# Arturo_Veras.net
KiCad netlist of a schematic drawn in EAGLE
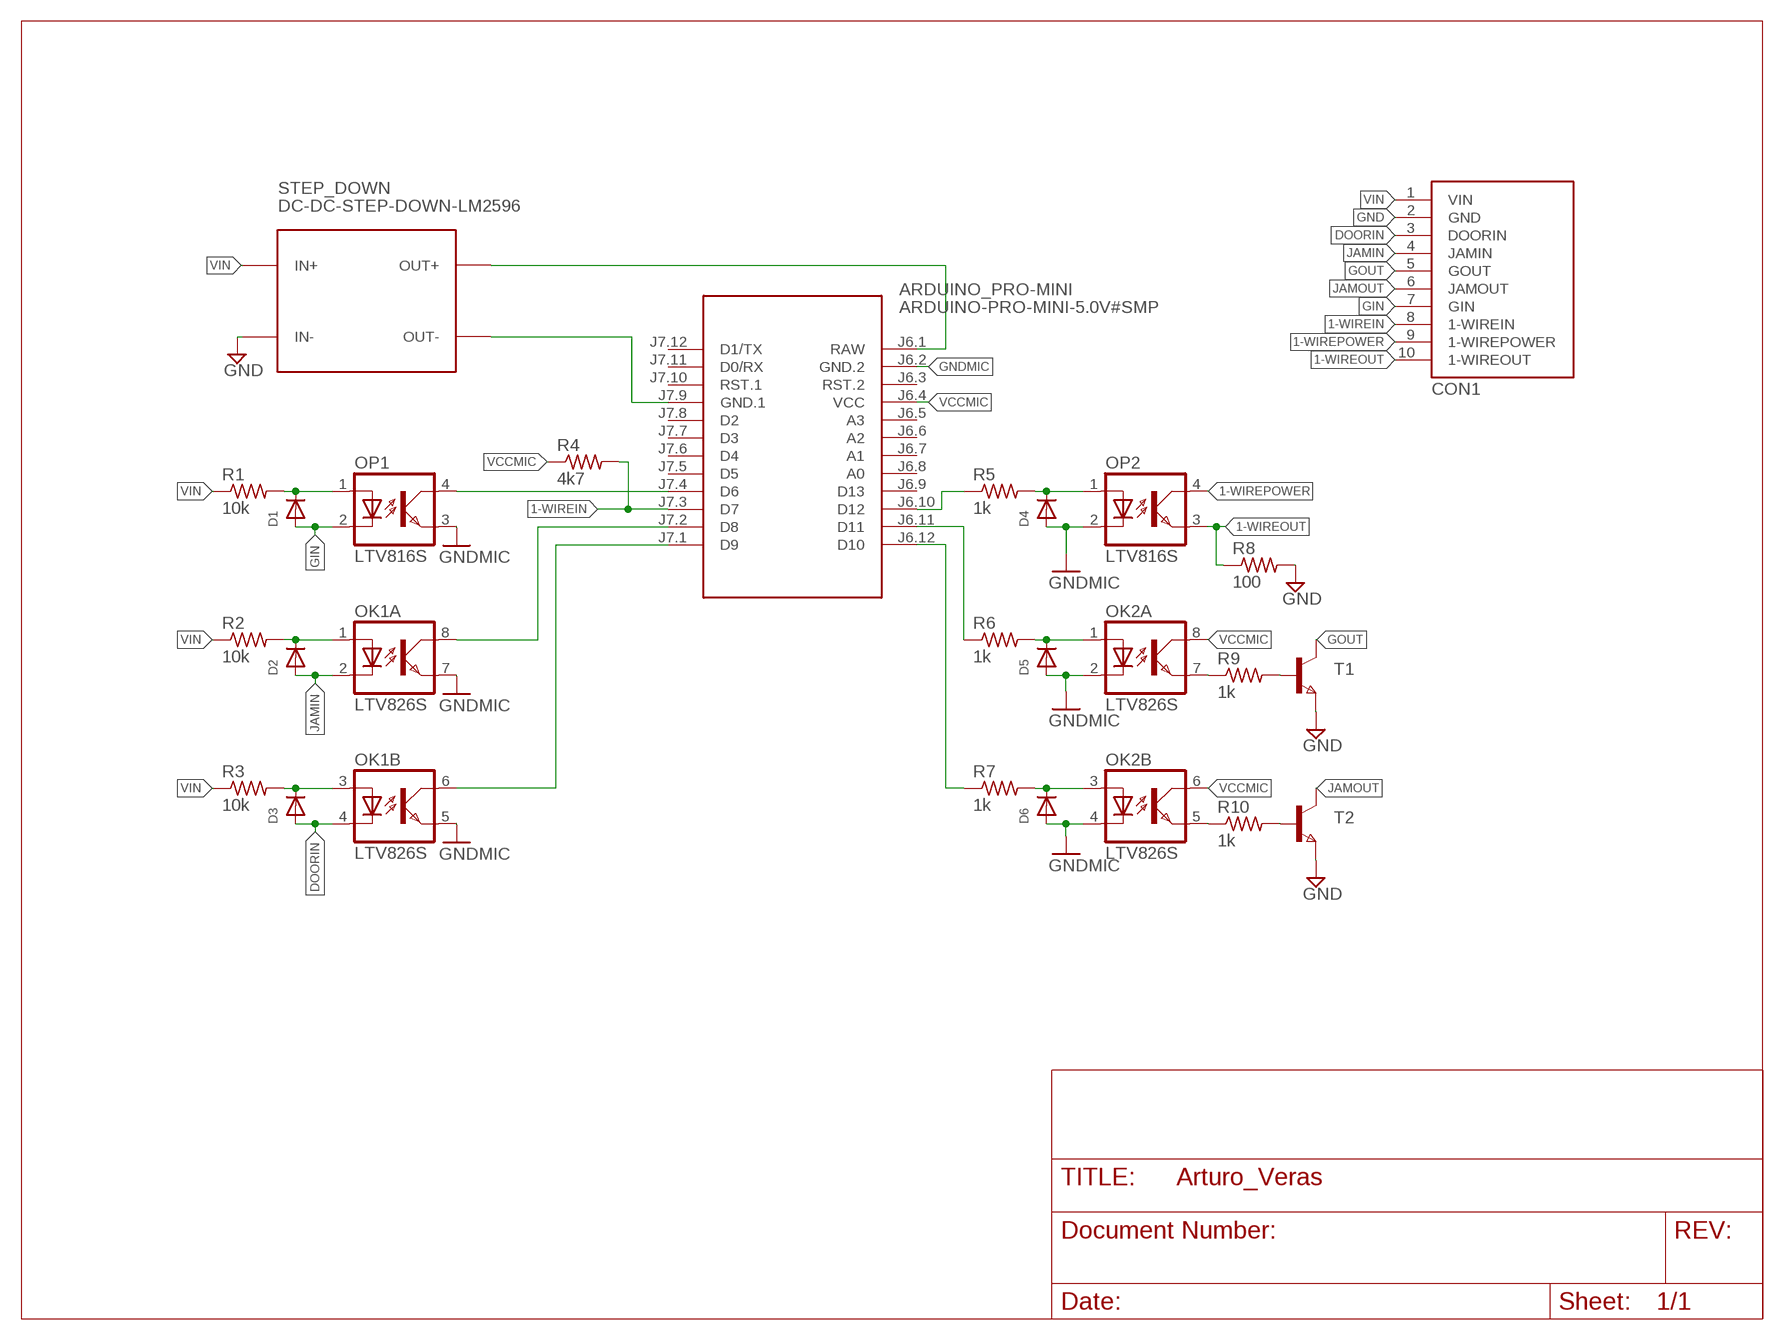
[diagram p0: schematic, sheet 1]

(export (version "E")
  (design (tool "Eeschema 10.0.6"))
  (components
    (comp (ref "ARDUINO_PRO-MINI")
      (value "ARDUINO-PRO-MINI-5.0V#SMP")
      (footprint "eagle-import:ARDUINO-PRO-MINI#SMP")
      (libsource (lib "eagle-import") (part "ARDUINO-PRO-MINI-#SMP5.0V"))
    )
    (comp (ref "CON1")
      (value "TIN_HEADER_10POS")
      (footprint "eagle-import:MICRO_MATE_N_LOK_TRUEHOLE_10POS")
      (libsource (lib "eagle-import") (part "TIN_HEADER_10POS"))
    )
    (comp (ref "D1")
      (value "DIODESOD-323F")
      (footprint "eagle-import:SOD-323F")
      (libsource (lib "eagle-import") (part "DIODESOD-323F"))
    )
    (comp (ref "D2")
      (value "DIODESOD-323F")
      (footprint "eagle-import:SOD-323F")
      (libsource (lib "eagle-import") (part "DIODESOD-323F"))
    )
    (comp (ref "D3")
      (value "DIODESOD-323F")
      (footprint "eagle-import:SOD-323F")
      (libsource (lib "eagle-import") (part "DIODESOD-323F"))
    )
    (comp (ref "D4")
      (value "DIODESOD-323F")
      (footprint "eagle-import:SOD-323F")
      (libsource (lib "eagle-import") (part "DIODESOD-323F"))
    )
    (comp (ref "D5")
      (value "DIODESOD-323F")
      (footprint "eagle-import:SOD-323F")
      (libsource (lib "eagle-import") (part "DIODESOD-323F"))
    )
    (comp (ref "D6")
      (value "DIODESOD-323F")
      (footprint "eagle-import:SOD-323F")
      (libsource (lib "eagle-import") (part "DIODESOD-323F"))
    )
    (comp (ref "OK1")
      (value "LTV826S")
      (footprint "eagle-import:DIL8-SMD")
      (libsource (lib "eagle-import") (part "LTV826S"))
    )
    (comp (ref "OK2")
      (value "LTV826S")
      (footprint "eagle-import:DIL8-SMD")
      (libsource (lib "eagle-import") (part "LTV826S"))
    )
    (comp (ref "OP1")
      (value "LTV816S")
      (footprint "eagle-import:SMD4")
      (libsource (lib "eagle-import") (part "LTV816S"))
    )
    (comp (ref "OP2")
      (value "LTV816S")
      (footprint "eagle-import:SMD4")
      (libsource (lib "eagle-import") (part "LTV816S"))
    )
    (comp (ref "R1")
      (value "10k")
      (footprint "eagle-import:R0603")
      (libsource (lib "eagle-import") (part "R-US_R0603"))
    )
    (comp (ref "R2")
      (value "10k")
      (footprint "eagle-import:R0603")
      (libsource (lib "eagle-import") (part "R-US_R0603"))
    )
    (comp (ref "R3")
      (value "10k")
      (footprint "eagle-import:R0603")
      (libsource (lib "eagle-import") (part "R-US_R0603"))
    )
    (comp (ref "R4")
      (value "4k7")
      (footprint "eagle-import:R0603")
      (libsource (lib "eagle-import") (part "R-US_R0603"))
    )
    (comp (ref "R5")
      (value "1k")
      (footprint "eagle-import:R0603")
      (libsource (lib "eagle-import") (part "R-US_R0603"))
    )
    (comp (ref "R6")
      (value "1k")
      (footprint "eagle-import:R0603")
      (libsource (lib "eagle-import") (part "R-US_R0603"))
    )
    (comp (ref "R7")
      (value "1k")
      (footprint "eagle-import:R0603")
      (libsource (lib "eagle-import") (part "R-US_R0603"))
    )
    (comp (ref "R8")
      (value "100")
      (footprint "eagle-import:R0603")
      (libsource (lib "eagle-import") (part "R-US_R0603"))
    )
    (comp (ref "R9")
      (value "1k")
      (footprint "eagle-import:R0603")
      (libsource (lib "eagle-import") (part "R-US_R0603"))
    )
    (comp (ref "R10")
      (value "1k")
      (footprint "eagle-import:R0603")
      (libsource (lib "eagle-import") (part "R-US_R0603"))
    )
    (comp (ref "STEP_DOWN")
      (value "DC-DC-STEP-DOWN-LM2596")
      (footprint "eagle-import:DC-DC-STEP-DOWN-LM2596")
      (libsource (lib "eagle-import") (part "DC-DC-STEP-DOWN-LM2596"))
    )
    (comp (ref "T1")
      (value "PBSS4360Z")
      (footprint "eagle-import:SOT223")
      (libsource (lib "eagle-import") (part "PBSS4360Z"))
    )
    (comp (ref "T2")
      (value "PBSS4360Z")
      (footprint "eagle-import:SOT223")
      (libsource (lib "eagle-import") (part "PBSS4360Z"))
    )
  )
  (nets
    (net (code "1") (name "1-WIREIN") (class "Default")
      (node (ref "ARDUINO_PRO-MINI") (pin "J7.3") (pinfunction "D7_J7.3") (pintype "bidirectional"))
      (node (ref "CON1") (pin "8") (pinfunction "1-WIREIN_8") (pintype "bidirectional"))
      (node (ref "R4") (pin "2") (pinfunction "2_2") (pintype "passive"))
    )
    (net (code "2") (name "1-WIREOUT") (class "Default")
      (node (ref "CON1") (pin "10") (pinfunction "1-WIREOUT_10") (pintype "bidirectional"))
      (node (ref "OP2") (pin "3") (pinfunction "EMIT_3") (pintype "passive"))
      (node (ref "R8") (pin "1") (pinfunction "1_1") (pintype "passive"))
    )
    (net (code "3") (name "1-WIREPOWER") (class "Default")
      (node (ref "CON1") (pin "9") (pinfunction "1-WIREPOWER_9") (pintype "bidirectional"))
      (node (ref "OP2") (pin "4") (pinfunction "COL_4") (pintype "passive"))
    )
    (net (code "4") (name "DOORIN") (class "Default")
      (node (ref "CON1") (pin "3") (pinfunction "DOORIN_3") (pintype "bidirectional"))
      (node (ref "D3") (pin "A") (pinfunction "A_A") (pintype "passive"))
      (node (ref "OK1") (pin "4") (pinfunction "C_4") (pintype "passive"))
    )
    (net (code "5") (name "GIN") (class "Default")
      (node (ref "CON1") (pin "7") (pinfunction "GIN_7") (pintype "bidirectional"))
      (node (ref "D1") (pin "A") (pinfunction "A_A") (pintype "passive"))
      (node (ref "OP1") (pin "2") (pinfunction "C_2") (pintype "passive"))
    )
    (net (code "6") (name "GND") (class "Default")
      (node (ref "CON1") (pin "2") (pinfunction "GND_2") (pintype "bidirectional"))
      (node (ref "R8") (pin "2") (pinfunction "2_2") (pintype "passive"))
      (node (ref "STEP_DOWN") (pin "IN-") (pinfunction "IN-_IN-") (pintype "bidirectional"))
      (node (ref "T1") (pin "3") (pinfunction "E_3") (pintype "passive"))
      (node (ref "T2") (pin "3") (pinfunction "E_3") (pintype "passive"))
    )
    (net (code "7") (name "GNDMIC") (class "Default")
      (node (ref "ARDUINO_PRO-MINI") (pin "J6.2") (pinfunction "GND.2_J6.2") (pintype "power_in"))
      (node (ref "D4") (pin "A") (pinfunction "A_A") (pintype "passive"))
      (node (ref "D5") (pin "A") (pinfunction "A_A") (pintype "passive"))
      (node (ref "D6") (pin "A") (pinfunction "A_A") (pintype "passive"))
      (node (ref "OK1") (pin "5") (pinfunction "EMIT_5") (pintype "passive"))
      (node (ref "OK1") (pin "7") (pinfunction "EMIT_7") (pintype "passive"))
      (node (ref "OK2") (pin "2") (pinfunction "C_2") (pintype "passive"))
      (node (ref "OK2") (pin "4") (pinfunction "C_4") (pintype "passive"))
      (node (ref "OP1") (pin "3") (pinfunction "EMIT_3") (pintype "passive"))
      (node (ref "OP2") (pin "2") (pinfunction "C_2") (pintype "passive"))
    )
    (net (code "8") (name "GOUT") (class "Default")
      (node (ref "CON1") (pin "5") (pinfunction "GOUT_5") (pintype "bidirectional"))
      (node (ref "T1") (pin "2") (pinfunction "C_2") (pintype "passive"))
      (node (ref "T1") (pin "4") (pinfunction "C_4") (pintype "passive"))
    )
    (net (code "9") (name "JAMIN") (class "Default")
      (node (ref "CON1") (pin "4") (pinfunction "JAMIN_4") (pintype "bidirectional"))
      (node (ref "D2") (pin "A") (pinfunction "A_A") (pintype "passive"))
      (node (ref "OK1") (pin "2") (pinfunction "C_2") (pintype "passive"))
    )
    (net (code "10") (name "JAMOUT") (class "Default")
      (node (ref "CON1") (pin "6") (pinfunction "JAMOUT_6") (pintype "bidirectional"))
      (node (ref "T2") (pin "2") (pinfunction "C_2") (pintype "passive"))
      (node (ref "T2") (pin "4") (pinfunction "C_4") (pintype "passive"))
    )
    (net (code "11") (name "Net-(ARDUINO_PRO-MINI-D6)") (class "Default")
      (node (ref "ARDUINO_PRO-MINI") (pin "J7.4") (pinfunction "D6_J7.4") (pintype "bidirectional"))
      (node (ref "OP1") (pin "4") (pinfunction "COL_4") (pintype "passive"))
    )
    (net (code "12") (name "Net-(ARDUINO_PRO-MINI-D8)") (class "Default")
      (node (ref "ARDUINO_PRO-MINI") (pin "J7.2") (pinfunction "D8_J7.2") (pintype "bidirectional"))
      (node (ref "OK1") (pin "8") (pinfunction "COL_8") (pintype "passive"))
    )
    (net (code "13") (name "Net-(ARDUINO_PRO-MINI-D9)") (class "Default")
      (node (ref "ARDUINO_PRO-MINI") (pin "J7.1") (pinfunction "D9_J7.1") (pintype "bidirectional"))
      (node (ref "OK1") (pin "6") (pinfunction "COL_6") (pintype "passive"))
    )
    (net (code "14") (name "Net-(ARDUINO_PRO-MINI-D10)") (class "Default")
      (node (ref "ARDUINO_PRO-MINI") (pin "J6.12") (pinfunction "D10_J6.12") (pintype "bidirectional"))
      (node (ref "R7") (pin "1") (pinfunction "1_1") (pintype "passive"))
    )
    (net (code "15") (name "Net-(ARDUINO_PRO-MINI-D11)") (class "Default")
      (node (ref "ARDUINO_PRO-MINI") (pin "J6.11") (pinfunction "D11_J6.11") (pintype "bidirectional"))
      (node (ref "R6") (pin "1") (pinfunction "1_1") (pintype "passive"))
    )
    (net (code "16") (name "Net-(ARDUINO_PRO-MINI-D12)") (class "Default")
      (node (ref "ARDUINO_PRO-MINI") (pin "J6.10") (pinfunction "D12_J6.10") (pintype "bidirectional"))
      (node (ref "R5") (pin "1") (pinfunction "1_1") (pintype "passive"))
    )
    (net (code "17") (name "Net-(ARDUINO_PRO-MINI-GND.1)") (class "Default")
      (node (ref "ARDUINO_PRO-MINI") (pin "J7.9") (pinfunction "GND.1_J7.9") (pintype "power_in"))
      (node (ref "STEP_DOWN") (pin "OUT-") (pinfunction "OUT-_OUT-") (pintype "bidirectional"))
    )
    (net (code "18") (name "Net-(ARDUINO_PRO-MINI-RAW)") (class "Default")
      (node (ref "ARDUINO_PRO-MINI") (pin "J6.1") (pinfunction "RAW_J6.1") (pintype "power_in"))
      (node (ref "STEP_DOWN") (pin "OUT+") (pinfunction "OUT+_OUT+") (pintype "bidirectional"))
    )
    (net (code "19") (name "Net-(OK1A-A)") (class "Default")
      (node (ref "D2") (pin "C") (pinfunction "C_C") (pintype "passive"))
      (node (ref "OK1") (pin "1") (pinfunction "A_1") (pintype "passive"))
      (node (ref "R2") (pin "2") (pinfunction "2_2") (pintype "passive"))
    )
    (net (code "20") (name "Net-(OK1B-A)") (class "Default")
      (node (ref "D3") (pin "C") (pinfunction "C_C") (pintype "passive"))
      (node (ref "OK1") (pin "3") (pinfunction "A_3") (pintype "passive"))
      (node (ref "R3") (pin "2") (pinfunction "2_2") (pintype "passive"))
    )
    (net (code "21") (name "Net-(OK2A-A)") (class "Default")
      (node (ref "D5") (pin "C") (pinfunction "C_C") (pintype "passive"))
      (node (ref "OK2") (pin "1") (pinfunction "A_1") (pintype "passive"))
      (node (ref "R6") (pin "2") (pinfunction "2_2") (pintype "passive"))
    )
    (net (code "22") (name "Net-(OK2A-EMIT)") (class "Default")
      (node (ref "OK2") (pin "7") (pinfunction "EMIT_7") (pintype "passive"))
      (node (ref "R9") (pin "1") (pinfunction "1_1") (pintype "passive"))
    )
    (net (code "23") (name "Net-(OK2B-A)") (class "Default")
      (node (ref "D6") (pin "C") (pinfunction "C_C") (pintype "passive"))
      (node (ref "OK2") (pin "3") (pinfunction "A_3") (pintype "passive"))
      (node (ref "R7") (pin "2") (pinfunction "2_2") (pintype "passive"))
    )
    (net (code "24") (name "Net-(OK2B-EMIT)") (class "Default")
      (node (ref "OK2") (pin "5") (pinfunction "EMIT_5") (pintype "passive"))
      (node (ref "R10") (pin "1") (pinfunction "1_1") (pintype "passive"))
    )
    (net (code "25") (name "Net-(OP1-A)") (class "Default")
      (node (ref "D1") (pin "C") (pinfunction "C_C") (pintype "passive"))
      (node (ref "OP1") (pin "1") (pinfunction "A_1") (pintype "passive"))
      (node (ref "R1") (pin "2") (pinfunction "2_2") (pintype "passive"))
    )
    (net (code "26") (name "Net-(OP2-A)") (class "Default")
      (node (ref "D4") (pin "C") (pinfunction "C_C") (pintype "passive"))
      (node (ref "OP2") (pin "1") (pinfunction "A_1") (pintype "passive"))
      (node (ref "R5") (pin "2") (pinfunction "2_2") (pintype "passive"))
    )
    (net (code "27") (name "Net-(T1-B)") (class "Default")
      (node (ref "R9") (pin "2") (pinfunction "2_2") (pintype "passive"))
      (node (ref "T1") (pin "1") (pinfunction "B_1") (pintype "passive"))
    )
    (net (code "28") (name "Net-(T2-B)") (class "Default")
      (node (ref "R10") (pin "2") (pinfunction "2_2") (pintype "passive"))
      (node (ref "T2") (pin "1") (pinfunction "B_1") (pintype "passive"))
    )
    (net (code "29") (name "VCCMIC") (class "Default")
      (node (ref "ARDUINO_PRO-MINI") (pin "J6.4") (pinfunction "VCC_J6.4") (pintype "power_in"))
      (node (ref "OK2") (pin "6") (pinfunction "COL_6") (pintype "passive"))
      (node (ref "OK2") (pin "8") (pinfunction "COL_8") (pintype "passive"))
      (node (ref "R4") (pin "1") (pinfunction "1_1") (pintype "passive"))
    )
    (net (code "30") (name "VIN") (class "Default")
      (node (ref "CON1") (pin "1") (pinfunction "VIN_1") (pintype "bidirectional"))
      (node (ref "R1") (pin "1") (pinfunction "1_1") (pintype "passive"))
      (node (ref "R2") (pin "1") (pinfunction "1_1") (pintype "passive"))
      (node (ref "R3") (pin "1") (pinfunction "1_1") (pintype "passive"))
      (node (ref "STEP_DOWN") (pin "IN+") (pinfunction "IN+_IN+") (pintype "bidirectional"))
    )
    (net (code "31") (name "unconnected-(ARDUINO_PRO-MINI-A0-PadJ6.8)") (class "Default")
      (node (ref "ARDUINO_PRO-MINI") (pin "J6.8") (pinfunction "A0_J6.8") (pintype "bidirectional"))
    )
    (net (code "32") (name "unconnected-(ARDUINO_PRO-MINI-A1-PadJ6.7)") (class "Default")
      (node (ref "ARDUINO_PRO-MINI") (pin "J6.7") (pinfunction "A1_J6.7") (pintype "bidirectional"))
    )
    (net (code "33") (name "unconnected-(ARDUINO_PRO-MINI-A2-PadJ6.6)") (class "Default")
      (node (ref "ARDUINO_PRO-MINI") (pin "J6.6") (pinfunction "A2_J6.6") (pintype "bidirectional"))
    )
    (net (code "34") (name "unconnected-(ARDUINO_PRO-MINI-A3-PadJ6.5)") (class "Default")
      (node (ref "ARDUINO_PRO-MINI") (pin "J6.5") (pinfunction "A3_J6.5") (pintype "bidirectional"))
    )
    (net (code "35") (name "unconnected-(ARDUINO_PRO-MINI-D0{slash}RX-PadJ7.11)") (class "Default")
      (node (ref "ARDUINO_PRO-MINI") (pin "J7.11") (pinfunction "D0/RX_J7.11") (pintype "bidirectional"))
    )
    (net (code "36") (name "unconnected-(ARDUINO_PRO-MINI-D1{slash}TX-PadJ7.12)") (class "Default")
      (node (ref "ARDUINO_PRO-MINI") (pin "J7.12") (pinfunction "D1/TX_J7.12") (pintype "bidirectional"))
    )
    (net (code "37") (name "unconnected-(ARDUINO_PRO-MINI-D2-PadJ7.8)") (class "Default")
      (node (ref "ARDUINO_PRO-MINI") (pin "J7.8") (pinfunction "D2_J7.8") (pintype "bidirectional"))
    )
    (net (code "38") (name "unconnected-(ARDUINO_PRO-MINI-D3-PadJ7.7)") (class "Default")
      (node (ref "ARDUINO_PRO-MINI") (pin "J7.7") (pinfunction "D3_J7.7") (pintype "bidirectional"))
    )
    (net (code "39") (name "unconnected-(ARDUINO_PRO-MINI-D4-PadJ7.6)") (class "Default")
      (node (ref "ARDUINO_PRO-MINI") (pin "J7.6") (pinfunction "D4_J7.6") (pintype "bidirectional"))
    )
    (net (code "40") (name "unconnected-(ARDUINO_PRO-MINI-D5-PadJ7.5)") (class "Default")
      (node (ref "ARDUINO_PRO-MINI") (pin "J7.5") (pinfunction "D5_J7.5") (pintype "bidirectional"))
    )
    (net (code "41") (name "unconnected-(ARDUINO_PRO-MINI-D13-PadJ6.9)") (class "Default")
      (node (ref "ARDUINO_PRO-MINI") (pin "J6.9") (pinfunction "D13_J6.9") (pintype "bidirectional"))
    )
    (net (code "42") (name "unconnected-(ARDUINO_PRO-MINI-RST.1-PadJ7.10)") (class "Default")
      (node (ref "ARDUINO_PRO-MINI") (pin "J7.10") (pinfunction "RST.1_J7.10") (pintype "bidirectional"))
    )
    (net (code "43") (name "unconnected-(ARDUINO_PRO-MINI-RST.2-PadJ6.3)") (class "Default")
      (node (ref "ARDUINO_PRO-MINI") (pin "J6.3") (pinfunction "RST.2_J6.3") (pintype "bidirectional"))
    )
  )
)
